# F401.net
KiCad netlist of a schematic drawn in EasyEDA Pro
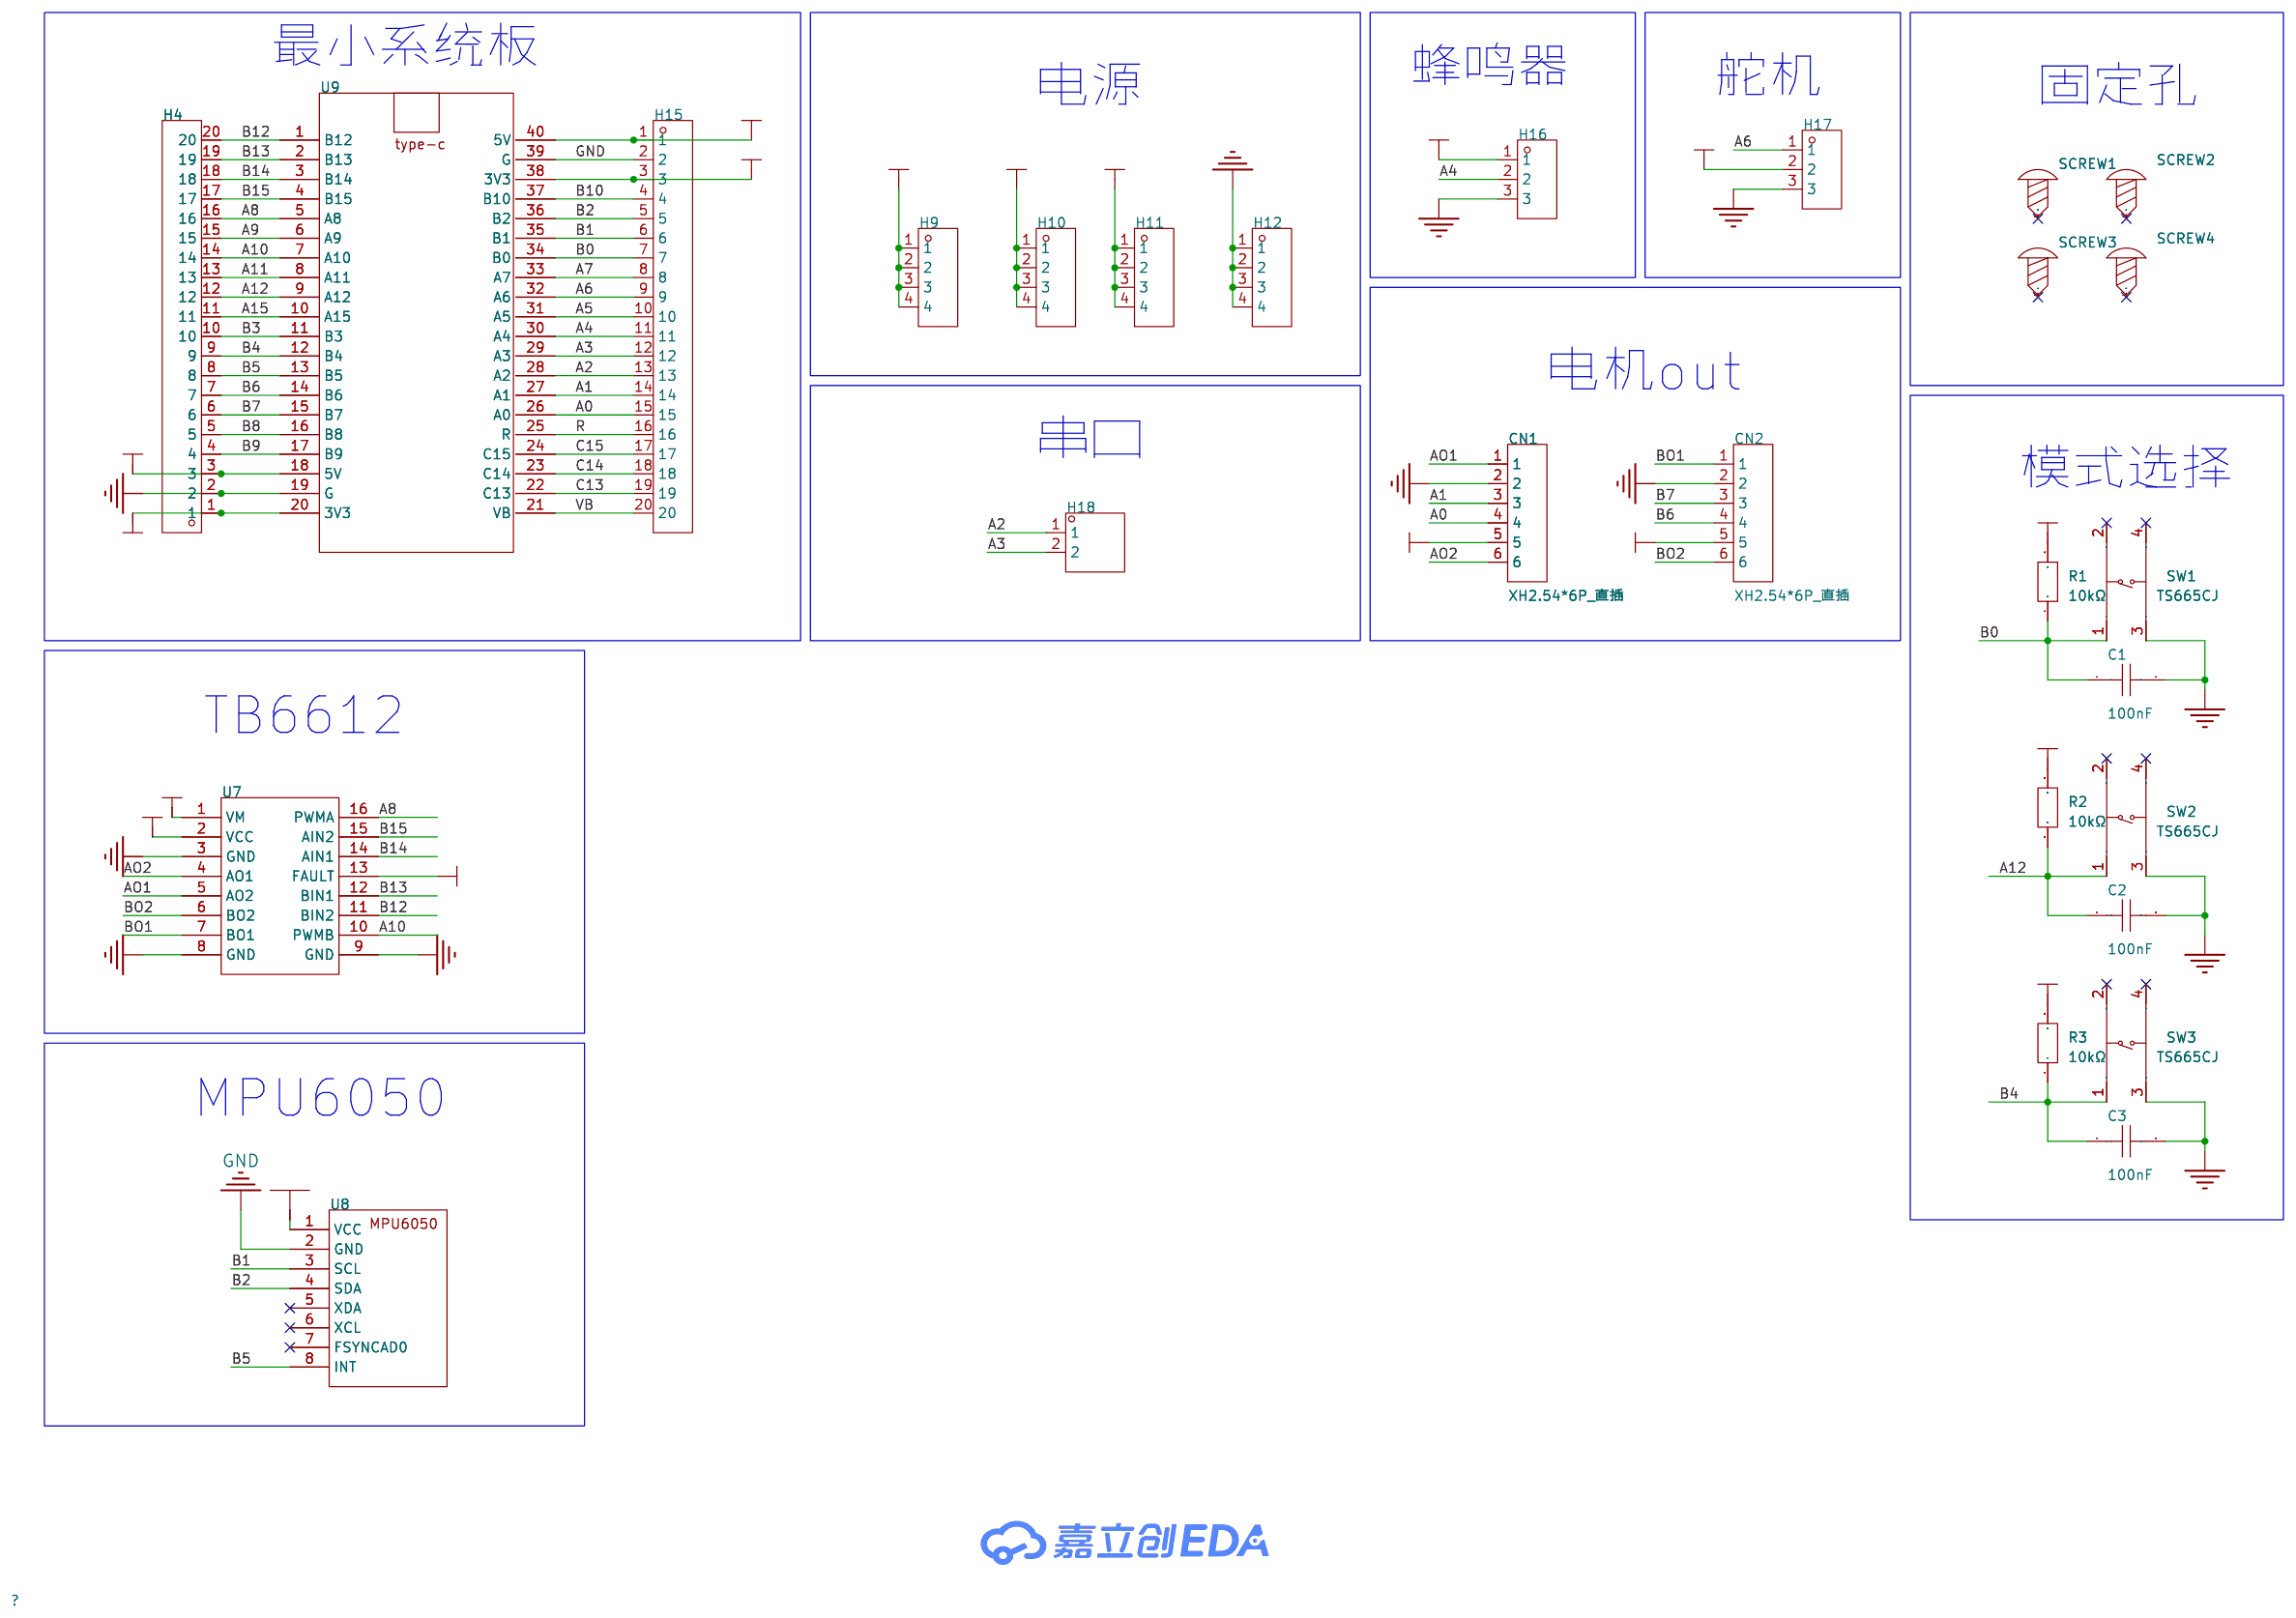
[diagram p0: schematic sheet]

(export (version "E")
  (design (tool "Eeschema 10.0.6"))
  (components
    (comp (ref "C1")
      (value "100nF")
      (footprint "easyedapro:CAP-TH_L5.0-W2.5-P5.00-D1.0")
      (description "容值:100nF;精度:±20%;额定电压:50V;温度系数:Y5V;")
      (fields
        (field (name "Manufacturer Part") "CC1H104MC1FD3F6C10MF")
        (field (name "Manufacturer") "Dersonic(德尔创)")
      )
      (libsource (lib "easyedapro") (part "CC1H104MC1FD3F6C10MF"))
    )
    (comp (ref "C2")
      (value "100nF")
      (footprint "easyedapro:CAP-TH_L5.0-W2.5-P5.00-D1.0")
      (description "容值:100nF;精度:±20%;额定电压:50V;温度系数:Y5V;")
      (fields
        (field (name "Manufacturer Part") "CC1H104MC1FD3F6C10MF")
        (field (name "Manufacturer") "Dersonic(德尔创)")
      )
      (libsource (lib "easyedapro") (part "CC1H104MC1FD3F6C10MF"))
    )
    (comp (ref "C3")
      (value "100nF")
      (footprint "easyedapro:CAP-TH_L5.0-W2.5-P5.00-D1.0")
      (description "容值:100nF;精度:±20%;额定电压:50V;温度系数:Y5V;")
      (fields
        (field (name "Manufacturer Part") "CC1H104MC1FD3F6C10MF")
        (field (name "Manufacturer") "Dersonic(德尔创)")
      )
      (libsource (lib "easyedapro") (part "CC1H104MC1FD3F6C10MF"))
    )
    (comp (ref "CN1")
      (value "XH2.54*6P_直插")
      (footprint "easyedapro:CONN-TH_XH2.54-6P")
      (libsource (lib "easyedapro") (part "XH2.54*6P_直插"))
    )
    (comp (ref "CN2")
      (value "XH2.54*6P_直插")
      (footprint "easyedapro:CONN-TH_XH2.54-6P")
      (libsource (lib "easyedapro") (part "XH2.54*6P_直插"))
    )
    (comp (ref "H4")
      (value "~")
      (footprint "easyedapro:HDR-TH_20P-P2.54-V-M-1")
      (libsource (lib "easyedapro") (part "HDR_2.54-1x20P"))
    )
    (comp (ref "H9")
      (value "~")
      (footprint "easyedapro:HDR-TH_4P-P2.54-V-M")
      (libsource (lib "easyedapro") (part "PZ254V-11-04P"))
    )
    (comp (ref "H10")
      (value "~")
      (footprint "easyedapro:HDR-TH_4P-P2.54-V-M")
      (libsource (lib "easyedapro") (part "PZ254V-11-04P"))
    )
    (comp (ref "H11")
      (value "~")
      (footprint "easyedapro:HDR-TH_4P-P2.54-V-M")
      (libsource (lib "easyedapro") (part "PZ254V-11-04P"))
    )
    (comp (ref "H12")
      (value "~")
      (footprint "easyedapro:HDR-TH_4P-P2.54-V-M")
      (libsource (lib "easyedapro") (part "PZ254V-11-04P"))
    )
    (comp (ref "H15")
      (value "~")
      (footprint "easyedapro:HDR-TH_20P-P2.54-V-M-1")
      (libsource (lib "easyedapro") (part "HDR_2.54-1x20P"))
    )
    (comp (ref "H16")
      (value "~")
      (footprint "easyedapro:HDR-TH_3P-P2.54-V-F")
      (libsource (lib "easyedapro") (part "PM254V-11-03-H85"))
    )
    (comp (ref "H17")
      (value "~")
      (footprint "easyedapro:HDR-TH_3P-P2.54-V-M")
      (libsource (lib "easyedapro") (part "PZ254V-11-03P_C2937625"))
    )
    (comp (ref "H18")
      (value "~")
      (footprint "easyedapro:HDR-TH_2P-P2.54-V-M-1")
      (libsource (lib "easyedapro") (part "210S-1*2P L=11.6MMGold-plated black"))
    )
    (comp (ref "R1")
      (value "10kΩ")
      (footprint "easyedapro:RES-TH_BD2.7-L6.2-P10.20-D0.4")
      (description "电阻类型:金属膜电阻;阻值:1kΩ;精度:±1%;功率:250mW;温度系数:±100ppm/°C;")
      (fields (field (name "Manufacturer Part") "MF1/4W-1K±1%-ST52") (field (name "Manufacturer") "VO(翔胜)"))
      (libsource (lib "easyedapro") (part "MF1/4W-1K±1%-ST52"))
    )
    (comp (ref "R2")
      (value "10kΩ")
      (footprint "easyedapro:RES-TH_BD2.7-L6.2-P10.20-D0.4")
      (description "电阻类型:金属膜电阻;阻值:1kΩ;精度:±1%;功率:250mW;温度系数:±100ppm/°C;")
      (fields (field (name "Manufacturer Part") "MF1/4W-1K±1%-ST52") (field (name "Manufacturer") "VO(翔胜)"))
      (libsource (lib "easyedapro") (part "MF1/4W-1K±1%-ST52"))
    )
    (comp (ref "R3")
      (value "10kΩ")
      (footprint "easyedapro:RES-TH_BD2.7-L6.2-P10.20-D0.4")
      (description "电阻类型:金属膜电阻;阻值:1kΩ;精度:±1%;功率:250mW;温度系数:±100ppm/°C;")
      (fields (field (name "Manufacturer Part") "MF1/4W-1K±1%-ST52") (field (name "Manufacturer") "VO(翔胜)"))
      (libsource (lib "easyedapro") (part "MF1/4W-1K±1%-ST52"))
    )
    (comp (ref "SCREW1")
      (value "~")
      (footprint "easyedapro:M3螺丝")
      (libsource (lib "easyedapro") (part "螺丝孔"))
    )
    (comp (ref "SCREW2")
      (value "~")
      (footprint "easyedapro:M3螺丝")
      (libsource (lib "easyedapro") (part "螺丝孔"))
    )
    (comp (ref "SCREW3")
      (value "~")
      (footprint "easyedapro:M3螺丝")
      (libsource (lib "easyedapro") (part "螺丝孔"))
    )
    (comp (ref "SCREW4")
      (value "~")
      (footprint "easyedapro:M3螺丝")
      (libsource (lib "easyedapro") (part "螺丝孔"))
    )
    (comp (ref "SW1")
      (value "TS665CJ")
      (footprint "easyedapro:SW-TH_4P-L6.0-W6.0-P4.50-LS6.5")
      (description "电路结构:单刀单掷;按钮形状:圆形按钮;安装方式:直插;开关长度:6mm;开关宽度:6mm;开关高度:5mm;触点电流:50mA;额定电压(DC):12V;带灯:-;机械寿命:-;")
      (fields (field (name "Manufacturer") "SHOU HAN(首韩)"))
      (libsource (lib "easyedapro") (part "TS665CJ"))
    )
    (comp (ref "SW2")
      (value "TS665CJ")
      (footprint "easyedapro:SW-TH_4P-L6.0-W6.0-P4.50-LS6.5")
      (description "电路结构:单刀单掷;按钮形状:圆形按钮;安装方式:直插;开关长度:6mm;开关宽度:6mm;开关高度:5mm;触点电流:50mA;额定电压(DC):12V;带灯:-;机械寿命:-;")
      (fields (field (name "Manufacturer") "SHOU HAN(首韩)"))
      (libsource (lib "easyedapro") (part "TS665CJ"))
    )
    (comp (ref "SW3")
      (value "TS665CJ")
      (footprint "easyedapro:SW-TH_4P-L6.0-W6.0-P4.50-LS6.5")
      (description "电路结构:单刀单掷;按钮形状:圆形按钮;安装方式:直插;开关长度:6mm;开关宽度:6mm;开关高度:5mm;触点电流:50mA;额定电压(DC):12V;带灯:-;机械寿命:-;")
      (fields (field (name "Manufacturer") "SHOU HAN(首韩)"))
      (libsource (lib "easyedapro") (part "TS665CJ"))
    )
    (comp (ref "U7")
      (value "~")
      (footprint "easyedapro:TB6612FNG")
      (libsource (lib "easyedapro") (part "TB6612FNG"))
    )
    (comp (ref "U8")
      (value "~")
      (footprint "easyedapro:MPU6050")
      (libsource (lib "easyedapro") (part "MPU6050"))
    )
    (comp (ref "U9")
      (value "~")
      (footprint "easyedapro:F401CCU6")
      (libsource (lib "easyedapro") (part "F401CCU6"))
    )
  )
  (nets
    (net (code "1") (name "/A0") (class "Default")
      (node (ref "CN1") (pin "4") (pinfunction "4_4") (pintype "unspecified"))
      (node (ref "H15") (pin "15") (pinfunction "15_15") (pintype "input"))
      (node (ref "U9") (pin "26") (pinfunction "A0_26") (pintype "input"))
    )
    (net (code "2") (name "/A1") (class "Default")
      (node (ref "CN1") (pin "3") (pinfunction "3_3") (pintype "unspecified"))
      (node (ref "H15") (pin "14") (pinfunction "14_14") (pintype "input"))
      (node (ref "U9") (pin "27") (pinfunction "A1_27") (pintype "input"))
    )
    (net (code "3") (name "/A2") (class "Default")
      (node (ref "H15") (pin "13") (pinfunction "13_13") (pintype "input"))
      (node (ref "H18") (pin "1") (pinfunction "1_1") (pintype "unspecified"))
      (node (ref "U9") (pin "28") (pinfunction "A2_28") (pintype "input"))
    )
    (net (code "4") (name "/A3") (class "Default")
      (node (ref "H15") (pin "12") (pinfunction "12_12") (pintype "input"))
      (node (ref "H18") (pin "2") (pinfunction "2_2") (pintype "unspecified"))
      (node (ref "U9") (pin "29") (pinfunction "A3_29") (pintype "input"))
    )
    (net (code "5") (name "/A4") (class "Default")
      (node (ref "H15") (pin "11") (pinfunction "11_11") (pintype "input"))
      (node (ref "H16") (pin "2") (pinfunction "2_2") (pintype "unspecified"))
      (node (ref "U9") (pin "30") (pinfunction "A4_30") (pintype "input"))
    )
    (net (code "6") (name "/A5") (class "Default")
      (node (ref "H15") (pin "10") (pinfunction "10_10") (pintype "input"))
      (node (ref "U9") (pin "31") (pinfunction "A5_31") (pintype "input"))
    )
    (net (code "7") (name "/A6") (class "Default")
      (node (ref "H15") (pin "9") (pinfunction "9_9") (pintype "input"))
      (node (ref "H17") (pin "1") (pinfunction "1_1") (pintype "input"))
      (node (ref "U9") (pin "32") (pinfunction "A6_32") (pintype "input"))
    )
    (net (code "8") (name "/A7") (class "Default")
      (node (ref "H15") (pin "8") (pinfunction "8_8") (pintype "input"))
      (node (ref "U9") (pin "33") (pinfunction "A7_33") (pintype "input"))
    )
    (net (code "9") (name "/A8") (class "Default")
      (node (ref "H4") (pin "16") (pinfunction "16_16") (pintype "input"))
      (node (ref "U7") (pin "16") (pinfunction "PWMA_16") (pintype "input"))
      (node (ref "U9") (pin "5") (pinfunction "A8_5") (pintype "input"))
    )
    (net (code "10") (name "/A9") (class "Default")
      (node (ref "H4") (pin "15") (pinfunction "15_15") (pintype "input"))
      (node (ref "U9") (pin "6") (pinfunction "A9_6") (pintype "input"))
    )
    (net (code "11") (name "/A10") (class "Default")
      (node (ref "H4") (pin "14") (pinfunction "14_14") (pintype "input"))
      (node (ref "U7") (pin "10") (pinfunction "PWMB_10") (pintype "input"))
      (node (ref "U9") (pin "7") (pinfunction "A10_7") (pintype "input"))
    )
    (net (code "12") (name "/A11") (class "Default")
      (node (ref "H4") (pin "13") (pinfunction "13_13") (pintype "input"))
      (node (ref "U9") (pin "8") (pinfunction "A11_8") (pintype "input"))
    )
    (net (code "13") (name "/A12") (class "Default")
      (node (ref "C2") (pin "1") (pinfunction "1_1") (pintype "unspecified"))
      (node (ref "H4") (pin "12") (pinfunction "12_12") (pintype "input"))
      (node (ref "R2") (pin "1") (pinfunction "1_1") (pintype "unspecified"))
      (node (ref "SW2") (pin "1") (pinfunction "A_1") (pintype "unspecified"))
      (node (ref "U9") (pin "9") (pinfunction "A12_9") (pintype "input"))
    )
    (net (code "14") (name "/A15") (class "Default")
      (node (ref "H4") (pin "11") (pinfunction "11_11") (pintype "input"))
      (node (ref "U9") (pin "10") (pinfunction "A15_10") (pintype "input"))
    )
    (net (code "15") (name "/AO1") (class "Default")
      (node (ref "CN1") (pin "1") (pinfunction "1_1") (pintype "unspecified"))
      (node (ref "U7") (pin "5") (pinfunction "AO2_5") (pintype "input"))
    )
    (net (code "16") (name "/AO2") (class "Default")
      (node (ref "CN1") (pin "6") (pinfunction "6_6") (pintype "unspecified"))
      (node (ref "U7") (pin "4") (pinfunction "AO1_4") (pintype "input"))
    )
    (net (code "17") (name "/B0") (class "Default")
      (node (ref "C1") (pin "1") (pinfunction "1_1") (pintype "unspecified"))
      (node (ref "H15") (pin "7") (pinfunction "7_7") (pintype "input"))
      (node (ref "R1") (pin "1") (pinfunction "1_1") (pintype "unspecified"))
      (node (ref "SW1") (pin "1") (pinfunction "A_1") (pintype "unspecified"))
      (node (ref "U9") (pin "34") (pinfunction "B0_34") (pintype "input"))
    )
    (net (code "18") (name "/B1") (class "Default")
      (node (ref "H15") (pin "6") (pinfunction "6_6") (pintype "input"))
      (node (ref "U8") (pin "3") (pinfunction "SCL_3") (pintype "input"))
      (node (ref "U9") (pin "35") (pinfunction "B1_35") (pintype "input"))
    )
    (net (code "19") (name "/B2") (class "Default")
      (node (ref "H15") (pin "5") (pinfunction "5_5") (pintype "input"))
      (node (ref "U8") (pin "4") (pinfunction "SDA_4") (pintype "input"))
      (node (ref "U9") (pin "36") (pinfunction "B2_36") (pintype "input"))
    )
    (net (code "20") (name "/B3") (class "Default")
      (node (ref "H4") (pin "10") (pinfunction "10_10") (pintype "input"))
      (node (ref "U9") (pin "11") (pinfunction "B3_11") (pintype "input"))
    )
    (net (code "21") (name "/B4") (class "Default")
      (node (ref "C3") (pin "1") (pinfunction "1_1") (pintype "unspecified"))
      (node (ref "H4") (pin "9") (pinfunction "9_9") (pintype "input"))
      (node (ref "R3") (pin "1") (pinfunction "1_1") (pintype "unspecified"))
      (node (ref "SW3") (pin "1") (pinfunction "A_1") (pintype "unspecified"))
      (node (ref "U9") (pin "12") (pinfunction "B4_12") (pintype "input"))
    )
    (net (code "22") (name "/B5") (class "Default")
      (node (ref "H4") (pin "8") (pinfunction "8_8") (pintype "input"))
      (node (ref "U8") (pin "8") (pinfunction "INT_8") (pintype "input"))
      (node (ref "U9") (pin "13") (pinfunction "B5_13") (pintype "input"))
    )
    (net (code "23") (name "/B6") (class "Default")
      (node (ref "CN2") (pin "4") (pinfunction "4_4") (pintype "unspecified"))
      (node (ref "H4") (pin "7") (pinfunction "7_7") (pintype "input"))
      (node (ref "U9") (pin "14") (pinfunction "B6_14") (pintype "input"))
    )
    (net (code "24") (name "/B7") (class "Default")
      (node (ref "CN2") (pin "3") (pinfunction "3_3") (pintype "unspecified"))
      (node (ref "H4") (pin "6") (pinfunction "6_6") (pintype "input"))
      (node (ref "U9") (pin "15") (pinfunction "B7_15") (pintype "input"))
    )
    (net (code "25") (name "/B8") (class "Default")
      (node (ref "H4") (pin "5") (pinfunction "5_5") (pintype "input"))
      (node (ref "U9") (pin "16") (pinfunction "B8_16") (pintype "input"))
    )
    (net (code "26") (name "/B9") (class "Default")
      (node (ref "H4") (pin "4") (pinfunction "4_4") (pintype "input"))
      (node (ref "U9") (pin "17") (pinfunction "B9_17") (pintype "input"))
    )
    (net (code "27") (name "/B10") (class "Default")
      (node (ref "H15") (pin "4") (pinfunction "4_4") (pintype "input"))
      (node (ref "U9") (pin "37") (pinfunction "B10_37") (pintype "input"))
    )
    (net (code "28") (name "/B12") (class "Default")
      (node (ref "H4") (pin "20") (pinfunction "20_20") (pintype "input"))
      (node (ref "U7") (pin "11") (pinfunction "BIN2_11") (pintype "input"))
      (node (ref "U9") (pin "1") (pinfunction "B12_1") (pintype "input"))
    )
    (net (code "29") (name "/B13") (class "Default")
      (node (ref "H4") (pin "19") (pinfunction "19_19") (pintype "input"))
      (node (ref "U7") (pin "12") (pinfunction "BIN1_12") (pintype "input"))
      (node (ref "U9") (pin "2") (pinfunction "B13_2") (pintype "input"))
    )
    (net (code "30") (name "/B14") (class "Default")
      (node (ref "H4") (pin "18") (pinfunction "18_18") (pintype "input"))
      (node (ref "U7") (pin "14") (pinfunction "AIN1_14") (pintype "input"))
      (node (ref "U9") (pin "3") (pinfunction "B14_3") (pintype "input"))
    )
    (net (code "31") (name "/B15") (class "Default")
      (node (ref "H4") (pin "17") (pinfunction "17_17") (pintype "input"))
      (node (ref "U7") (pin "15") (pinfunction "AIN2_15") (pintype "input"))
      (node (ref "U9") (pin "4") (pinfunction "B15_4") (pintype "input"))
    )
    (net (code "32") (name "/BO1") (class "Default")
      (node (ref "CN2") (pin "1") (pinfunction "1_1") (pintype "unspecified"))
      (node (ref "U7") (pin "7") (pinfunction "BO1_7") (pintype "input"))
    )
    (net (code "33") (name "/BO2") (class "Default")
      (node (ref "CN2") (pin "6") (pinfunction "6_6") (pintype "unspecified"))
      (node (ref "U7") (pin "6") (pinfunction "BO2_6") (pintype "input"))
    )
    (net (code "34") (name "/C13") (class "Default")
      (node (ref "H15") (pin "19") (pinfunction "19_19") (pintype "input"))
      (node (ref "U9") (pin "22") (pinfunction "C13_22") (pintype "input"))
    )
    (net (code "35") (name "/C14") (class "Default")
      (node (ref "H15") (pin "18") (pinfunction "18_18") (pintype "input"))
      (node (ref "U9") (pin "23") (pinfunction "C14_23") (pintype "input"))
    )
    (net (code "36") (name "/C15") (class "Default")
      (node (ref "H15") (pin "17") (pinfunction "17_17") (pintype "input"))
      (node (ref "U9") (pin "24") (pinfunction "C15_24") (pintype "input"))
    )
    (net (code "37") (name "/R") (class "Default")
      (node (ref "H15") (pin "16") (pinfunction "16_16") (pintype "input"))
      (node (ref "U9") (pin "25") (pinfunction "R_25") (pintype "input"))
    )
    (net (code "38") (name "/VB") (class "Default")
      (node (ref "H15") (pin "20") (pinfunction "20_20") (pintype "input"))
      (node (ref "U9") (pin "21") (pinfunction "VB_21") (pintype "input"))
    )
    (net (code "39") (name "3V3") (class "Default")
      (node (ref "H11") (pin "1") (pinfunction "1_1") (pintype "unspecified"))
      (node (ref "H11") (pin "2") (pinfunction "2_2") (pintype "unspecified"))
      (node (ref "H11") (pin "3") (pinfunction "3_3") (pintype "unspecified"))
      (node (ref "H11") (pin "4") (pinfunction "4_4") (pintype "unspecified"))
      (node (ref "H15") (pin "3") (pinfunction "3_3") (pintype "input"))
      (node (ref "H16") (pin "1") (pinfunction "1_1") (pintype "unspecified"))
      (node (ref "H4") (pin "1") (pinfunction "1_1") (pintype "input"))
      (node (ref "R1") (pin "2") (pinfunction "2_2") (pintype "unspecified"))
      (node (ref "R2") (pin "2") (pinfunction "2_2") (pintype "unspecified"))
      (node (ref "R3") (pin "2") (pinfunction "2_2") (pintype "unspecified"))
      (node (ref "U9") (pin "20") (pinfunction "3V3_20") (pintype "input"))
      (node (ref "U9") (pin "38") (pinfunction "3V3_38") (pintype "input"))
    )
    (net (code "40") (name "5V") (class "Default")
      (node (ref "CN1") (pin "5") (pinfunction "5_5") (pintype "unspecified"))
      (node (ref "CN2") (pin "5") (pinfunction "5_5") (pintype "unspecified"))
      (node (ref "H10") (pin "1") (pinfunction "1_1") (pintype "unspecified"))
      (node (ref "H10") (pin "2") (pinfunction "2_2") (pintype "unspecified"))
      (node (ref "H10") (pin "3") (pinfunction "3_3") (pintype "unspecified"))
      (node (ref "H10") (pin "4") (pinfunction "4_4") (pintype "unspecified"))
      (node (ref "H15") (pin "1") (pinfunction "1_1") (pintype "input"))
      (node (ref "H17") (pin "2") (pinfunction "2_2") (pintype "input"))
      (node (ref "H4") (pin "3") (pinfunction "3_3") (pintype "input"))
      (node (ref "U7") (pin "13") (pinfunction "FAULT_13") (pintype "input"))
      (node (ref "U7") (pin "2") (pinfunction "VCC_2") (pintype "input"))
      (node (ref "U8") (pin "1") (pinfunction "VCC_1") (pintype "input"))
      (node (ref "U9") (pin "18") (pinfunction "5V_18") (pintype "input"))
      (node (ref "U9") (pin "40") (pinfunction "5V_40") (pintype "input"))
    )
    (net (code "41") (name "12V") (class "Default")
      (node (ref "H9") (pin "1") (pinfunction "1_1") (pintype "unspecified"))
      (node (ref "H9") (pin "2") (pinfunction "2_2") (pintype "unspecified"))
      (node (ref "H9") (pin "3") (pinfunction "3_3") (pintype "unspecified"))
      (node (ref "H9") (pin "4") (pinfunction "4_4") (pintype "unspecified"))
      (node (ref "U7") (pin "1") (pinfunction "VM_1") (pintype "input"))
    )
    (net (code "42") (name "GND") (class "Default")
      (node (ref "C1") (pin "2") (pinfunction "2_2") (pintype "unspecified"))
      (node (ref "C2") (pin "2") (pinfunction "2_2") (pintype "unspecified"))
      (node (ref "C3") (pin "2") (pinfunction "2_2") (pintype "unspecified"))
      (node (ref "CN1") (pin "2") (pinfunction "2_2") (pintype "unspecified"))
      (node (ref "CN2") (pin "2") (pinfunction "2_2") (pintype "unspecified"))
      (node (ref "H12") (pin "1") (pinfunction "1_1") (pintype "unspecified"))
      (node (ref "H12") (pin "2") (pinfunction "2_2") (pintype "unspecified"))
      (node (ref "H12") (pin "3") (pinfunction "3_3") (pintype "unspecified"))
      (node (ref "H12") (pin "4") (pinfunction "4_4") (pintype "unspecified"))
      (node (ref "H15") (pin "2") (pinfunction "2_2") (pintype "input"))
      (node (ref "H16") (pin "3") (pinfunction "3_3") (pintype "unspecified"))
      (node (ref "H17") (pin "3") (pinfunction "3_3") (pintype "input"))
      (node (ref "H4") (pin "2") (pinfunction "2_2") (pintype "input"))
      (node (ref "SW1") (pin "3") (pinfunction "C_3") (pintype "unspecified"))
      (node (ref "SW2") (pin "3") (pinfunction "C_3") (pintype "unspecified"))
      (node (ref "SW3") (pin "3") (pinfunction "C_3") (pintype "unspecified"))
      (node (ref "U7") (pin "3") (pinfunction "GND_3") (pintype "input"))
      (node (ref "U7") (pin "8") (pinfunction "GND_8") (pintype "input"))
      (node (ref "U7") (pin "9") (pinfunction "GND_9") (pintype "input"))
      (node (ref "U8") (pin "2") (pinfunction "GND_2") (pintype "input"))
      (node (ref "U9") (pin "19") (pinfunction "G_19") (pintype "input"))
      (node (ref "U9") (pin "39") (pinfunction "G_39") (pintype "input"))
    )
    (net (code "43") (name "unconnected-(SCREW1-Pad1)") (class "Default")
      (node (ref "SCREW1") (pin "1") (pinfunction "1_1") (pintype "input+no_connect"))
    )
    (net (code "44") (name "unconnected-(SCREW2-Pad1)") (class "Default")
      (node (ref "SCREW2") (pin "1") (pinfunction "1_1") (pintype "input+no_connect"))
    )
    (net (code "45") (name "unconnected-(SCREW3-Pad1)") (class "Default")
      (node (ref "SCREW3") (pin "1") (pinfunction "1_1") (pintype "input+no_connect"))
    )
    (net (code "46") (name "unconnected-(SCREW4-Pad1)") (class "Default")
      (node (ref "SCREW4") (pin "1") (pinfunction "1_1") (pintype "input+no_connect"))
    )
    (net (code "47") (name "unconnected-(SW1-B-Pad2)") (class "Default")
      (node (ref "SW1") (pin "2") (pinfunction "B_2") (pintype "unspecified+no_connect"))
    )
    (net (code "48") (name "unconnected-(SW1-D-Pad4)") (class "Default")
      (node (ref "SW1") (pin "4") (pinfunction "D_4") (pintype "unspecified+no_connect"))
    )
    (net (code "49") (name "unconnected-(SW2-B-Pad2)") (class "Default")
      (node (ref "SW2") (pin "2") (pinfunction "B_2") (pintype "unspecified+no_connect"))
    )
    (net (code "50") (name "unconnected-(SW2-D-Pad4)") (class "Default")
      (node (ref "SW2") (pin "4") (pinfunction "D_4") (pintype "unspecified+no_connect"))
    )
    (net (code "51") (name "unconnected-(SW3-B-Pad2)") (class "Default")
      (node (ref "SW3") (pin "2") (pinfunction "B_2") (pintype "unspecified+no_connect"))
    )
    (net (code "52") (name "unconnected-(SW3-D-Pad4)") (class "Default")
      (node (ref "SW3") (pin "4") (pinfunction "D_4") (pintype "unspecified+no_connect"))
    )
    (net (code "53") (name "unconnected-(U8-FSYNCAD0-Pad7)") (class "Default")
      (node (ref "U8") (pin "7") (pinfunction "FSYNCAD0_7") (pintype "input+no_connect"))
    )
    (net (code "54") (name "unconnected-(U8-XCL-Pad6)") (class "Default")
      (node (ref "U8") (pin "6") (pinfunction "XCL_6") (pintype "input+no_connect"))
    )
    (net (code "55") (name "unconnected-(U8-XDA-Pad5)") (class "Default")
      (node (ref "U8") (pin "5") (pinfunction "XDA_5") (pintype "input+no_connect"))
    )
  )
)
